# Smartfin_Main_PCBA_USB.net
KiCad netlist of a schematic drawn in Altium Designer
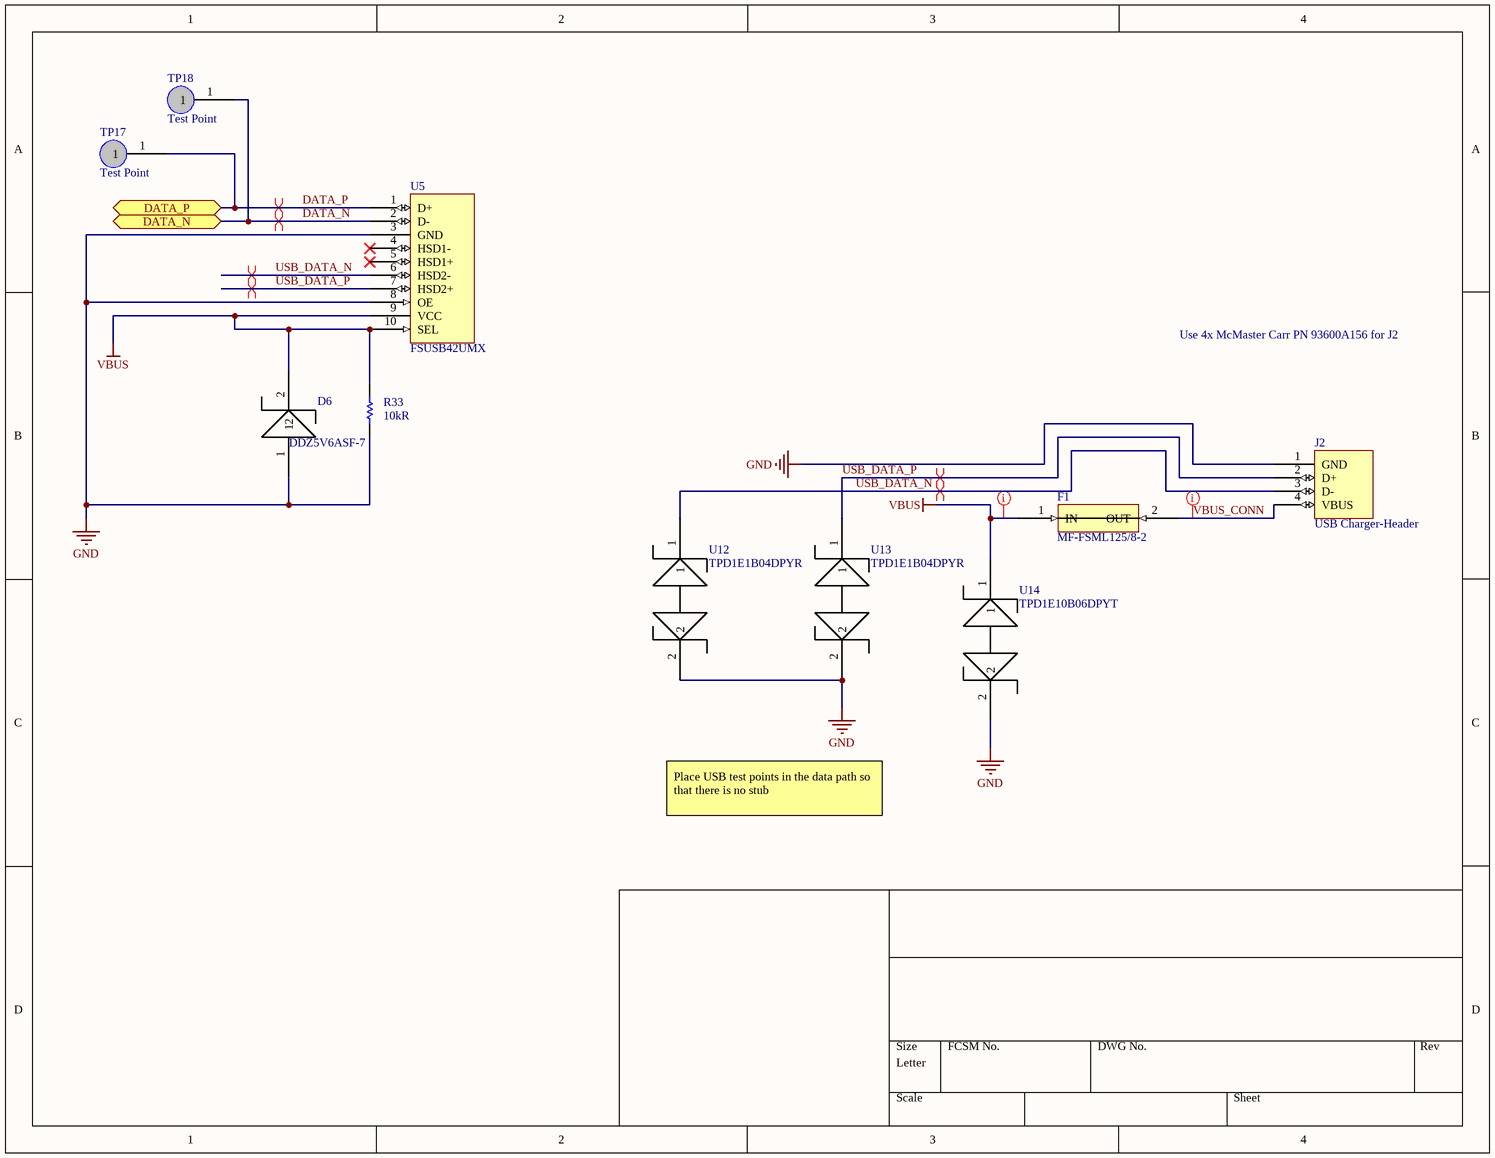
[diagram p0:  Smartfin Main PCBA USB.SchDoc]

(export (version "E")
  (design (tool "Eeschema 10.0.6"))
  (components
    (comp (ref "D6")
      (value "DDZ5V6ASF-7")
      (footprint "SODFL250X75-2N")
      (description "Zener Diode, 5.42V V(Z), 2.5%, 0.5W, Silicon")
      (libsource (lib "University of California, San Diego") (part "New symbol 1"))
    )
    (comp (ref "F1")
      (value "MF-FSML125/8-2")
      (footprint "CAF-50P85X165-2N")
      (libsource (lib "University of California, San Diego") (part "MF-FSML125_8-2-Symbol-1"))
    )
    (comp (ref "J2")
      (value "USB Charger-Header")
      (footprint "New footprint 1")
      (description "Smartfin USB Charger Header")
      (libsource (lib "") (part "New symbol 1_2"))
    )
    (comp (ref "R33")
      (value "10kR")
      (footprint "RESC1005X04N")
      (fields (field (name "Comment") "RC0402FR-0710KL"))
      (libsource (lib "University of California, San Diego") (part "RES"))
    )
    (comp (ref "TP17")
      (value "Test Point")
      (footprint "New footprint 1")
      (libsource (lib "") (part "New symbol 1_1"))
    )
    (comp (ref "TP18")
      (value "Test Point")
      (footprint "New footprint 1")
      (libsource (lib "") (part "New symbol 1_1"))
    )
    (comp (ref "U5")
      (value "FSUSB42UMX")
      (footprint "IC_FSUSB42UMX")
      (description "USB Switch IC 1 Channel 10-UMLP _1.8x1.4_")
      (fields (field (name "MF") "ON Semiconductor"))
      (libsource (lib "University of California, San Diego") (part "FSUSB42UMX-Symbol-1"))
    )
    (comp (ref "U12")
      (value "TPD1E1B04DPYR")
      (footprint "DIO_TPD1E05U06DPYR")
      (fields (field (name "MF") "Texas Instruments"))
      (libsource (lib "University of California, San Diego") (part "TPD1E1B04DPYR"))
    )
    (comp (ref "U13")
      (value "TPD1E1B04DPYR")
      (footprint "DIO_TPD1E05U06DPYR")
      (fields (field (name "MF") "Texas Instruments"))
      (libsource (lib "University of California, San Diego") (part "TPD1E1B04DPYR"))
    )
    (comp (ref "U14")
      (value "TPD1E10B06DPYT")
      (footprint "DIO_TPD1E05U06DPYR")
      (description "Single-channel ESD in 0402 package with 10pF capacitance and 6-V breakdown 2-X1SON -40 to 125")
      (fields (field (name "MF") "Texas Instruments") (field (name "DIGI-KEY_PART_NUMBER") "296-41842-1-ND"))
      (libsource (lib "University of California, San Diego") (part "TPD1E10B06DPYT"))
    )
  )
  (nets
    (net (code "1") (name "/DATA_N") (class "Default")
      (node (ref "TP18") (pin "1") (pinfunction "1_1") (pintype "passive"))
      (node (ref "U5") (pin "2") (pinfunction "D-_2") (pintype "bidirectional"))
    )
    (net (code "2") (name "/DATA_P") (class "Default")
      (node (ref "TP17") (pin "1") (pinfunction "1_1") (pintype "passive"))
      (node (ref "U5") (pin "1") (pinfunction "D+_1") (pintype "bidirectional"))
    )
    (net (code "3") (name "/USB_DATA_N") (class "Default")
      (node (ref "J2") (pin "3") (pinfunction "D-_3") (pintype "bidirectional"))
      (node (ref "U12") (pin "1") (pinfunction "1_1") (pintype "passive"))
      (node (ref "U5") (pin "6") (pinfunction "HSD2-_6") (pintype "bidirectional"))
    )
    (net (code "4") (name "/USB_DATA_P") (class "Default")
      (node (ref "J2") (pin "2") (pinfunction "D+_2") (pintype "bidirectional"))
      (node (ref "U13") (pin "1") (pinfunction "1_1") (pintype "passive"))
      (node (ref "U5") (pin "7") (pinfunction "HSD2+_7") (pintype "bidirectional"))
    )
    (net (code "5") (name "/VBUS_CONN") (class "Default")
      (node (ref "F1") (pin "2") (pinfunction "OUT_2") (pintype "input"))
      (node (ref "J2") (pin "4") (pinfunction "VBUS_4") (pintype "bidirectional"))
    )
    (net (code "6") (name "GND") (class "Default")
      (node (ref "D6") (pin "1") (pinfunction "1_1") (pintype "passive"))
      (node (ref "J2") (pin "1") (pinfunction "GND_1") (pintype "passive"))
      (node (ref "R33") (pin "1") (pinfunction "1_1") (pintype "passive"))
      (node (ref "U12") (pin "2") (pinfunction "2_2") (pintype "passive"))
      (node (ref "U13") (pin "2") (pinfunction "2_2") (pintype "passive"))
      (node (ref "U14") (pin "2") (pinfunction "2_2") (pintype "passive"))
      (node (ref "U5") (pin "3") (pinfunction "GND_3") (pintype "passive"))
      (node (ref "U5") (pin "8") (pinfunction "OE_8") (pintype "input"))
    )
    (net (code "7") (name "VBUS") (class "Default")
      (node (ref "D6") (pin "2") (pinfunction "2_2") (pintype "passive"))
      (node (ref "F1") (pin "1") (pinfunction "IN_1") (pintype "input"))
      (node (ref "R33") (pin "2") (pinfunction "2_2") (pintype "passive"))
      (node (ref "U14") (pin "1") (pinfunction "1_1") (pintype "passive"))
      (node (ref "U5") (pin "10") (pinfunction "SEL_10") (pintype "input"))
      (node (ref "U5") (pin "9") (pinfunction "VCC_9") (pintype "power_in"))
    )
    (net (code "8") (name "unconnected-(U5-HSD1+-Pad5)") (class "Default")
      (node (ref "U5") (pin "5") (pinfunction "HSD1+_5") (pintype "bidirectional+no_connect"))
    )
    (net (code "9") (name "unconnected-(U5-HSD1--Pad4)") (class "Default")
      (node (ref "U5") (pin "4") (pinfunction "HSD1-_4") (pintype "bidirectional+no_connect"))
    )
  )
)
